# Pedals_Inline_Test_Board_rev1.net
KiCad netlist of a schematic drawn in EAGLE
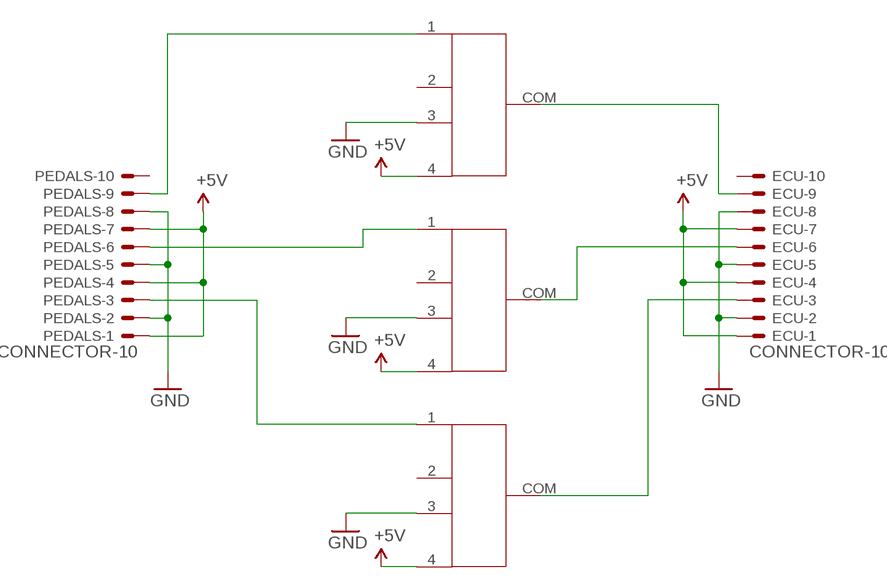
[diagram p0: schematic, sheet 1]

(export (version "E")
  (design (tool "Eeschema 10.0.6"))
  (components
    (comp (ref "ECU")
      (value "CONNECTOR-10")
      (footprint "eagle-import:MINIFIT_5566-10")
      (libsource (lib "eagle-import") (part "CONNECTOR-10"))
    )
    (comp (ref "PEDALS")
      (value "CONNECTOR-10")
      (footprint "eagle-import:MINIFIT_5566-10")
      (libsource (lib "eagle-import") (part "CONNECTOR-10"))
    )
    (comp (ref "U$1")
      (value "SS-14D0839-VG5PA")
      (footprint "eagle-import:SS-14D0839-VG5PA")
      (libsource (lib "eagle-import") (part "SS-14D0839-VG5PA"))
    )
    (comp (ref "U$2")
      (value "SS-14D0839-VG5PA")
      (footprint "eagle-import:SS-14D0839-VG5PA")
      (libsource (lib "eagle-import") (part "SS-14D0839-VG5PA"))
    )
    (comp (ref "U$3")
      (value "SS-14D0839-VG5PA")
      (footprint "eagle-import:SS-14D0839-VG5PA")
      (libsource (lib "eagle-import") (part "SS-14D0839-VG5PA"))
    )
  )
  (nets
    (net (code "1") (name "+5V") (class "Default")
      (node (ref "ECU") (pin "1") (pinfunction "S_1") (pintype "passive"))
      (node (ref "ECU") (pin "4") (pinfunction "S_4") (pintype "passive"))
      (node (ref "ECU") (pin "7") (pinfunction "S_7") (pintype "passive"))
      (node (ref "PEDALS") (pin "1") (pinfunction "S_1") (pintype "passive"))
      (node (ref "PEDALS") (pin "4") (pinfunction "S_4") (pintype "passive"))
      (node (ref "PEDALS") (pin "7") (pinfunction "S_7") (pintype "passive"))
      (node (ref "U$1") (pin "4") (pinfunction "4_4") (pintype "bidirectional"))
      (node (ref "U$2") (pin "4") (pinfunction "4_4") (pintype "bidirectional"))
      (node (ref "U$3") (pin "4") (pinfunction "4_4") (pintype "bidirectional"))
    )
    (net (code "2") (name "GND") (class "Default")
      (node (ref "ECU") (pin "2") (pinfunction "S_2") (pintype "passive"))
      (node (ref "ECU") (pin "5") (pinfunction "S_5") (pintype "passive"))
      (node (ref "ECU") (pin "8") (pinfunction "S_8") (pintype "passive"))
      (node (ref "PEDALS") (pin "2") (pinfunction "S_2") (pintype "passive"))
      (node (ref "PEDALS") (pin "5") (pinfunction "S_5") (pintype "passive"))
      (node (ref "PEDALS") (pin "8") (pinfunction "S_8") (pintype "passive"))
      (node (ref "U$1") (pin "3") (pinfunction "3_3") (pintype "bidirectional"))
      (node (ref "U$2") (pin "3") (pinfunction "3_3") (pintype "bidirectional"))
      (node (ref "U$3") (pin "3") (pinfunction "3_3") (pintype "bidirectional"))
    )
    (net (code "3") (name "Net-(ECUD-S)") (class "Default")
      (node (ref "ECU") (pin "3") (pinfunction "S_3") (pintype "passive"))
      (node (ref "U$3") (pin "COM") (pinfunction "COM_COM") (pintype "bidirectional"))
    )
    (net (code "4") (name "Net-(ECUG-S)") (class "Default")
      (node (ref "ECU") (pin "6") (pinfunction "S_6") (pintype "passive"))
      (node (ref "U$2") (pin "COM") (pinfunction "COM_COM") (pintype "bidirectional"))
    )
    (net (code "5") (name "Net-(ECUJ-S)") (class "Default")
      (node (ref "ECU") (pin "9") (pinfunction "S_9") (pintype "passive"))
      (node (ref "U$1") (pin "COM") (pinfunction "COM_COM") (pintype "bidirectional"))
    )
    (net (code "6") (name "Net-(PEDALSD-S)") (class "Default")
      (node (ref "PEDALS") (pin "3") (pinfunction "S_3") (pintype "passive"))
      (node (ref "U$3") (pin "1") (pinfunction "1_1") (pintype "bidirectional"))
    )
    (net (code "7") (name "Net-(PEDALSG-S)") (class "Default")
      (node (ref "PEDALS") (pin "6") (pinfunction "S_6") (pintype "passive"))
      (node (ref "U$2") (pin "1") (pinfunction "1_1") (pintype "bidirectional"))
    )
    (net (code "8") (name "Net-(PEDALSJ-S)") (class "Default")
      (node (ref "PEDALS") (pin "9") (pinfunction "S_9") (pintype "passive"))
      (node (ref "U$1") (pin "1") (pinfunction "1_1") (pintype "bidirectional"))
    )
    (net (code "9") (name "unconnected-(ECUB-S-Pad10)") (class "Default")
      (node (ref "ECU") (pin "10") (pinfunction "S_10") (pintype "passive"))
    )
    (net (code "10") (name "unconnected-(PEDALSB-S-Pad10)") (class "Default")
      (node (ref "PEDALS") (pin "10") (pinfunction "S_10") (pintype "passive"))
    )
    (net (code "11") (name "unconnected-(U$1-Pad2)") (class "Default")
      (node (ref "U$1") (pin "2") (pinfunction "2_2") (pintype "bidirectional"))
    )
    (net (code "12") (name "unconnected-(U$2-Pad2)") (class "Default")
      (node (ref "U$2") (pin "2") (pinfunction "2_2") (pintype "bidirectional"))
    )
    (net (code "13") (name "unconnected-(U$3-Pad2)") (class "Default")
      (node (ref "U$3") (pin "2") (pinfunction "2_2") (pintype "bidirectional"))
    )
  )
)
